# InkTime_schematic.net
KiCad netlist of a schematic drawn in EAGLE
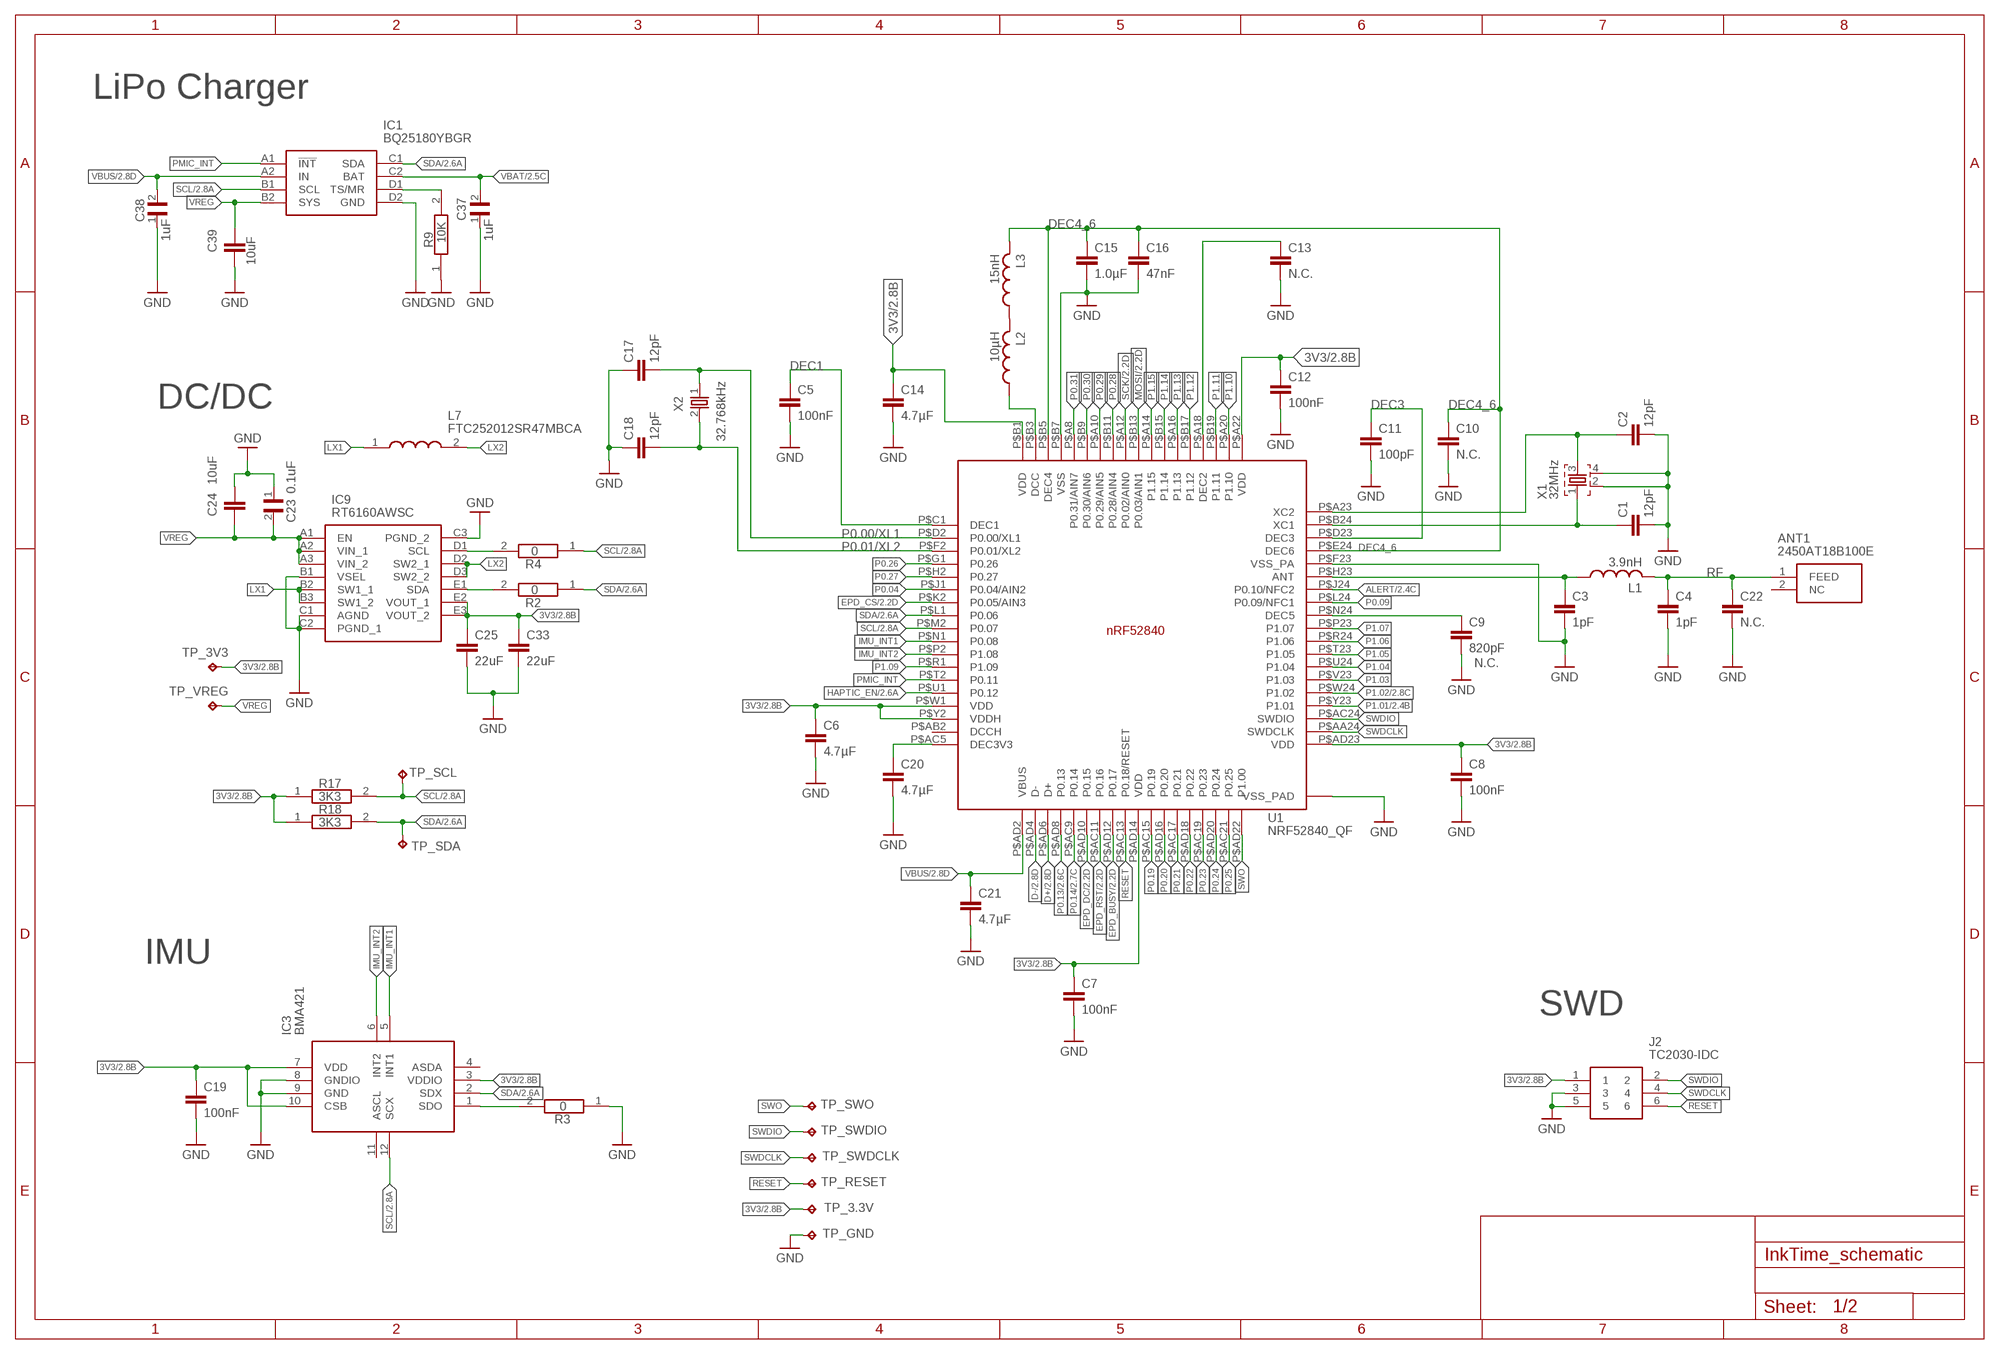
[diagram p0: schematic, sheet 1]
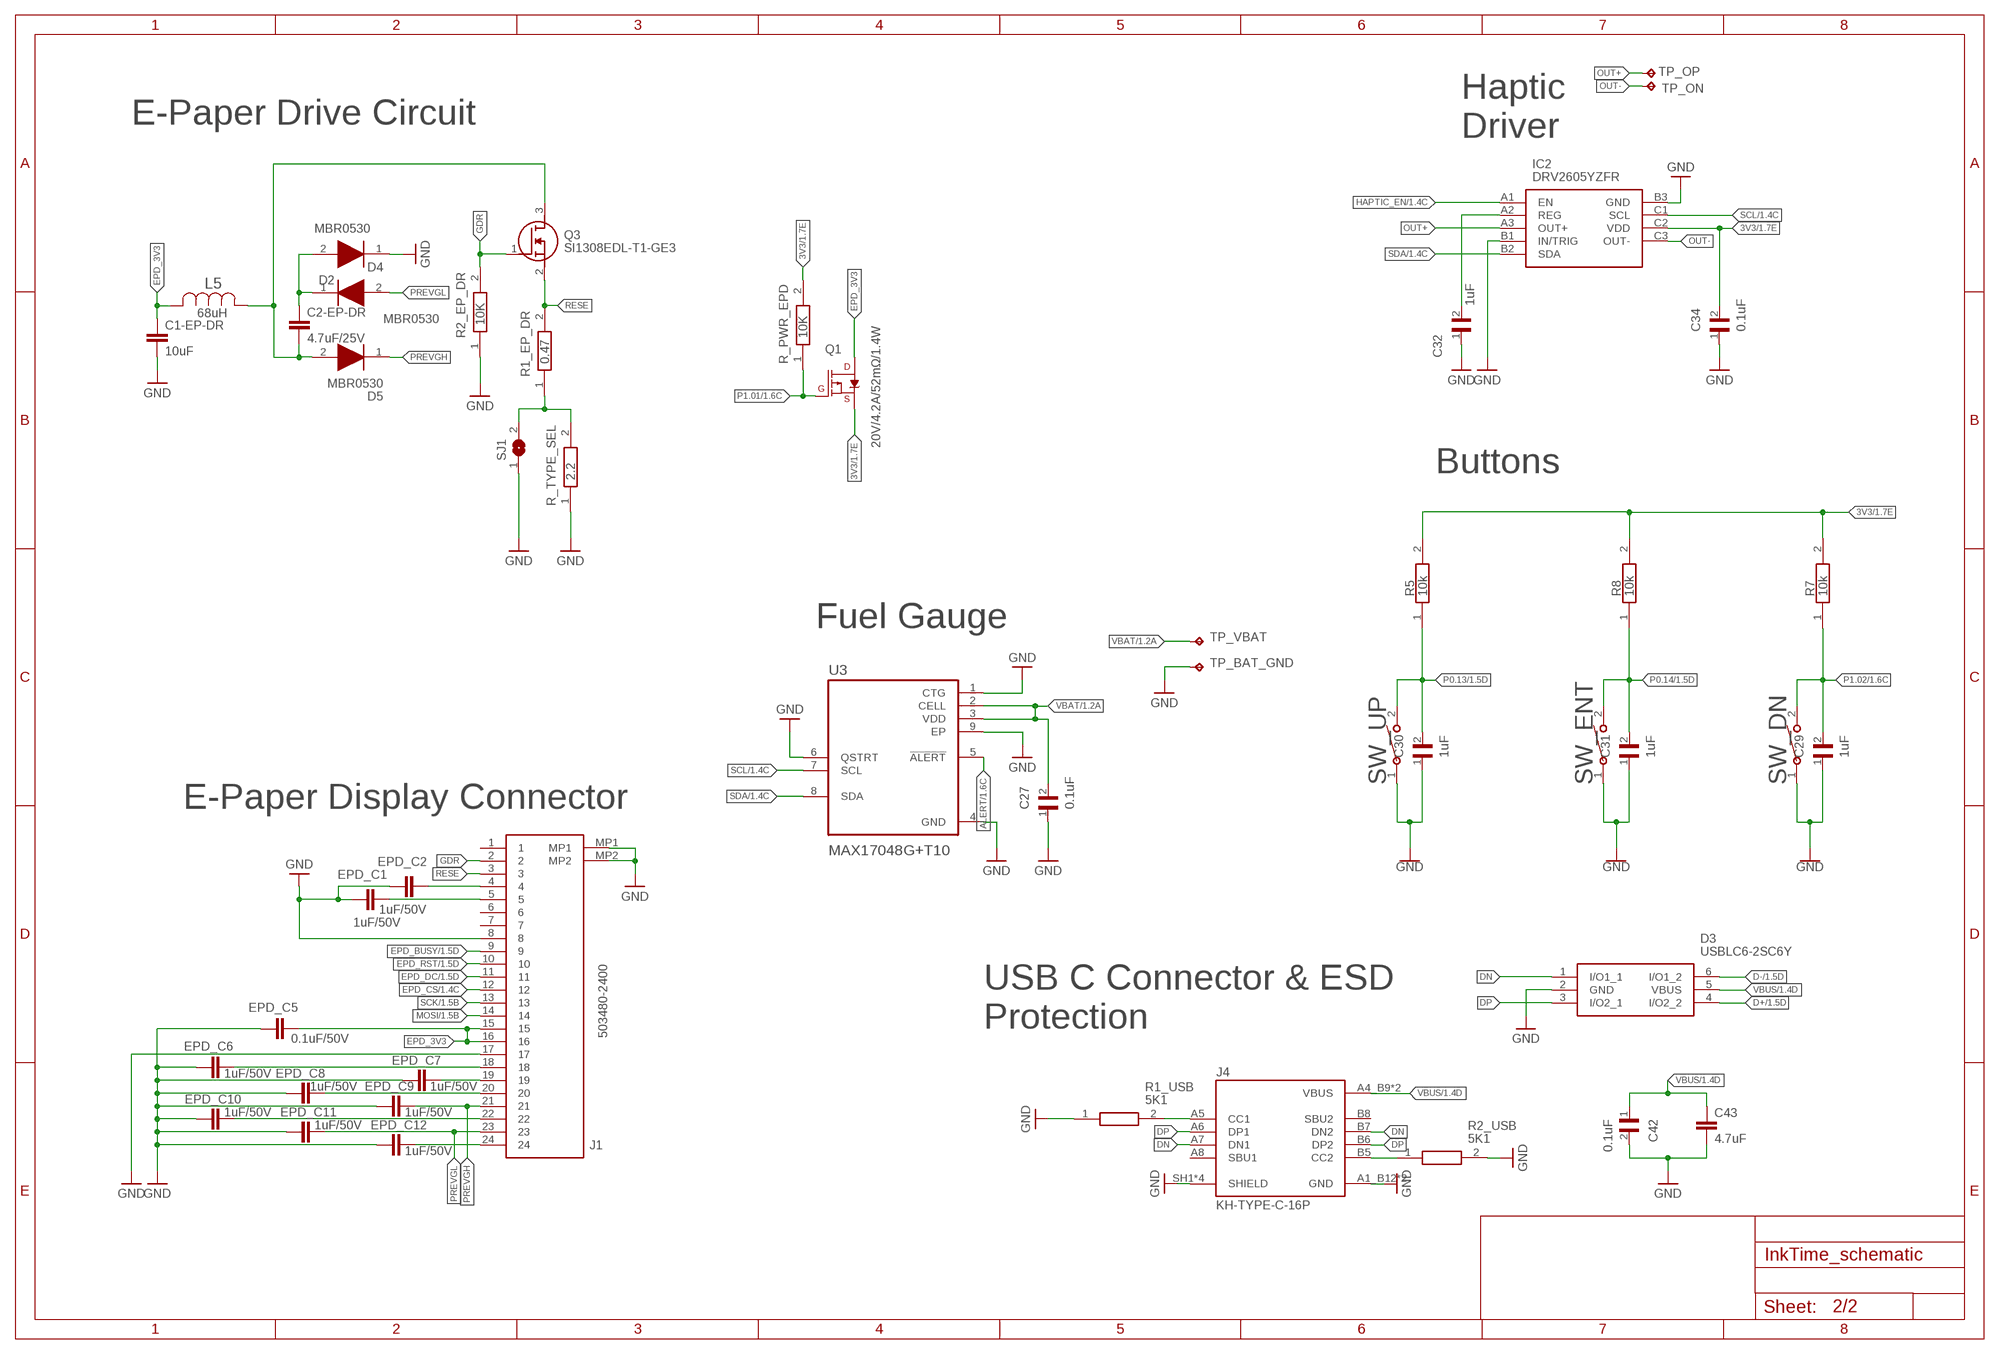
[diagram p1: schematic, sheet 2]

(export (version "E")
  (design (tool "Eeschema 10.0.6"))
  (components
    (comp (ref "ANT1")
      (value "2450AT18B100E")
      (footprint "eagle-import:2450AT18B100E_ANTC3216X140N")
      (fields (field (name "MOUSER_PART_NUMBER") "609-2450AT18B100E"))
      (libsource (lib "eagle-import") (part "2450AT18B100E_2450AT18B100E"))
    )
    (comp (ref "C1")
      (value "12pF")
      (footprint "eagle-import:NORDIC_NRF_3_RESC0201_L")
      (libsource (lib "eagle-import") (part "NORDIC_NRF_3_CAPACITOR_0201_L"))
    )
    (comp (ref "C2")
      (value "12pF")
      (footprint "eagle-import:NORDIC_NRF_3_RESC0201_L")
      (libsource (lib "eagle-import") (part "NORDIC_NRF_3_CAPACITOR_0201_L"))
    )
    (comp (ref "C3")
      (value "1pF")
      (footprint "eagle-import:NORDIC_NRF_3_RESC0201_L")
      (libsource (lib "eagle-import") (part "NORDIC_NRF_3_CAPACITOR_0201_L"))
    )
    (comp (ref "C4")
      (value "1pF")
      (footprint "eagle-import:NORDIC_NRF_3_RESC0201_L")
      (libsource (lib "eagle-import") (part "NORDIC_NRF_3_CAPACITOR_0201_L"))
    )
    (comp (ref "C5")
      (value "100nF")
      (footprint "eagle-import:NORDIC_NRF_3_RESC0201_L")
      (libsource (lib "eagle-import") (part "NORDIC_NRF_3_CAPACITOR_0201_L"))
    )
    (comp (ref "C6")
      (value "4.7µF")
      (footprint "eagle-import:NORDIC_NRF_3_RESC0201_L")
      (libsource (lib "eagle-import") (part "NORDIC_NRF_3_CAPACITOR_0201_L"))
    )
    (comp (ref "C7")
      (value "100nF")
      (footprint "eagle-import:NORDIC_NRF_3_RESC0201_L")
      (libsource (lib "eagle-import") (part "NORDIC_NRF_3_CAPACITOR_0201_L"))
    )
    (comp (ref "C8")
      (value "100nF")
      (footprint "eagle-import:NORDIC_NRF_3_RESC0201_L")
      (libsource (lib "eagle-import") (part "NORDIC_NRF_3_CAPACITOR_0201_L"))
    )
    (comp (ref "C9")
      (value "820pF")
      (footprint "eagle-import:NORDIC_NRF_3_RESC0201_L")
      (fields (field (name "STATUS") "N.C."))
      (libsource (lib "eagle-import") (part "NORDIC_NRF_3_CAPACITOR_0201_L"))
    )
    (comp (ref "C10")
      (value "N.C.")
      (footprint "eagle-import:NORDIC_NRF_3_RESC0201_L")
      (libsource (lib "eagle-import") (part "NORDIC_NRF_3_CAPACITOR_0201_L"))
    )
    (comp (ref "C11")
      (value "100pF")
      (footprint "eagle-import:NORDIC_NRF_3_RESC0201_L")
      (libsource (lib "eagle-import") (part "NORDIC_NRF_3_CAPACITOR_0201_L"))
    )
    (comp (ref "C12")
      (value "100nF")
      (footprint "eagle-import:NORDIC_NRF_3_RESC0201_L")
      (libsource (lib "eagle-import") (part "NORDIC_NRF_3_CAPACITOR_0201_L"))
    )
    (comp (ref "C13")
      (value "N.C.")
      (footprint "eagle-import:NORDIC_NRF_3_RESC0201_L")
      (libsource (lib "eagle-import") (part "NORDIC_NRF_3_CAPACITOR_0201_L"))
    )
    (comp (ref "C14")
      (value "4.7µF")
      (footprint "eagle-import:NORDIC_NRF_3_RESC0201_L")
      (libsource (lib "eagle-import") (part "NORDIC_NRF_3_CAPACITOR_0201_L"))
    )
    (comp (ref "C15")
      (value "1.0µF")
      (footprint "eagle-import:NORDIC_NRF_3_RESC0201_L")
      (libsource (lib "eagle-import") (part "NORDIC_NRF_3_CAPACITOR_0201_L"))
    )
    (comp (ref "C16")
      (value "47nF")
      (footprint "eagle-import:NORDIC_NRF_3_RESC0201_L")
      (libsource (lib "eagle-import") (part "NORDIC_NRF_3_CAPACITOR_0201_L"))
    )
    (comp (ref "C17")
      (value "12pF")
      (footprint "eagle-import:NORDIC_NRF_3_RESC0201_L")
      (libsource (lib "eagle-import") (part "NORDIC_NRF_3_CAPACITOR_0201_L"))
    )
    (comp (ref "C18")
      (value "12pF")
      (footprint "eagle-import:NORDIC_NRF_3_RESC0201_L")
      (libsource (lib "eagle-import") (part "NORDIC_NRF_3_CAPACITOR_0201_L"))
    )
    (comp (ref "C19")
      (value "100nF")
      (footprint "eagle-import:NORDIC_NRF_3_RESC0201_L")
      (libsource (lib "eagle-import") (part "NORDIC_NRF_3_CAPACITOR_0201_L"))
    )
    (comp (ref "C20")
      (value "4.7µF")
      (footprint "eagle-import:NORDIC_NRF_3_RESC0201_L")
      (libsource (lib "eagle-import") (part "NORDIC_NRF_3_CAPACITOR_0201_L"))
    )
    (comp (ref "C21")
      (value "4.7µF")
      (footprint "eagle-import:NORDIC_NRF_3_RESC0201_L")
      (libsource (lib "eagle-import") (part "NORDIC_NRF_3_CAPACITOR_0201_L"))
    )
    (comp (ref "C22")
      (value "N.C.")
      (footprint "eagle-import:NORDIC_NRF_3_RESC0201_L")
      (libsource (lib "eagle-import") (part "NORDIC_NRF_3_CAPACITOR_0201_L"))
    )
    (comp (ref "C23")
      (value "0.1uF")
      (footprint "eagle-import:GRM011R60J152KE01L_1_0201")
      (libsource (lib "eagle-import") (part "GRM011R60J152KE01L_1_GRM011R60J152KE01L"))
    )
    (comp (ref "C24")
      (value "10uF")
      (footprint "eagle-import:NORDIC_NRF_3_RESC0201_L")
      (libsource (lib "eagle-import") (part "NORDIC_NRF_3_CAPACITOR_0201_L"))
    )
    (comp (ref "C25")
      (value "22uF")
      (footprint "eagle-import:NORDIC_NRF_3_RESC0201_L")
      (libsource (lib "eagle-import") (part "NORDIC_NRF_3_CAPACITOR_0201_L"))
    )
    (comp (ref "C33")
      (value "22uF")
      (footprint "eagle-import:NORDIC_NRF_3_RESC0201_L")
      (libsource (lib "eagle-import") (part "NORDIC_NRF_3_CAPACITOR_0201_L"))
    )
    (comp (ref "C37")
      (value "1uF")
      (footprint "eagle-import:GRM011R60J152KE01L_1_0201")
      (libsource (lib "eagle-import") (part "GRM011R60J152KE01L_1_GRM011R60J152KE01L"))
    )
    (comp (ref "C38")
      (value "1uF")
      (footprint "eagle-import:GRM011R60J152KE01L_2_CAPC0201X13N")
      (fields (field (name "MF") "Murata") (field (name "MP") "GRM011R60J152KE01L"))
      (libsource (lib "eagle-import") (part "GRM011R60J152KE01L_2_GRM011R60J152KE01L"))
    )
    (comp (ref "C39")
      (value "10uF")
      (footprint "eagle-import:NORDIC_NRF_3_RESC0201_L")
      (libsource (lib "eagle-import") (part "NORDIC_NRF_3_CAPACITOR_0201_L"))
    )
    (comp (ref "IC1")
      (value "BQ25180YBGR")
      (footprint "eagle-import:BQ25180YBGR_BGA8C40P2X4_100X155X50")
      (fields (field (name "MOUSER_PART_NUMBER") "595-BQ25180YBGR"))
      (libsource (lib "eagle-import") (part "BQ25180YBGR_BQ25180YBGR"))
    )
    (comp (ref "IC3")
      (value "BMA421")
      (footprint "eagle-import:BMA423_BMA423")
      (fields (field (name "ARROW_PART_NUMBER") "BMA423") (field (name "MOUSER_PART_NUMBER") "262-BMA423"))
      (libsource (lib "eagle-import") (part "BMA423_BMA423"))
    )
    (comp (ref "IC9")
      (value "RT6160AWSC")
      (footprint "eagle-import:RT6160AWSC_BGA15C40P3X5_140X230X60")
      (fields (field (name "MOUSER_PART_NUMBER") "835-RT6160AWSC"))
      (libsource (lib "eagle-import") (part "RT6160AWSC_RT6160AWSC"))
    )
    (comp (ref "J2")
      (value "TC2030-IDC")
      (footprint "eagle-import:TC2030-IDC_TC2030IDC")
      (libsource (lib "eagle-import") (part "TC2030-IDC_TC2030-IDC"))
    )
    (comp (ref "L1")
      (value "3.9nH")
      (footprint "eagle-import:NORDIC_NRF_2_RESC0402_L")
      (libsource (lib "eagle-import") (part "NORDIC_NRF_2_INDUCTOR_0402_L"))
    )
    (comp (ref "L2")
      (value "10µH")
      (footprint "eagle-import:NORDIC_NRF_2_RESC0402_L")
      (libsource (lib "eagle-import") (part "NORDIC_NRF_2_INDUCTOR_0402_L"))
    )
    (comp (ref "L3")
      (value "15nH")
      (footprint "eagle-import:NORDIC_NRF_2_RESC0402_L")
      (libsource (lib "eagle-import") (part "NORDIC_NRF_2_INDUCTOR_0402_L"))
    )
    (comp (ref "L7")
      (value "FTC252012SR47MBCA")
      (footprint "eagle-import:MLP2016SR47MT0S1_INDC2016X100N")
      (libsource (lib "eagle-import") (part "MLP2016SR47MT0S1_FTC252012SR47MBCA"))
    )
    (comp (ref "R2")
      (value "0")
      (footprint "eagle-import:CPF0201D7K68C1_0201")
      (libsource (lib "eagle-import") (part "CPF0201D7K68C1_CPF0201D7K68C1"))
    )
    (comp (ref "R3")
      (value "0")
      (footprint "eagle-import:CPF0201D7K68C1_0201")
      (libsource (lib "eagle-import") (part "CPF0201D7K68C1_CPF0201D7K68C1"))
    )
    (comp (ref "R4")
      (value "0")
      (footprint "eagle-import:CPF0201D7K68C1_0201")
      (libsource (lib "eagle-import") (part "CPF0201D7K68C1_CPF0201D7K68C1"))
    )
    (comp (ref "R9")
      (value "10K")
      (footprint "eagle-import:CPF0201D7K68C1_0201")
      (libsource (lib "eagle-import") (part "CPF0201D7K68C1_CPF0201D7K68C1"))
    )
    (comp (ref "R17")
      (value "3K3")
      (footprint "eagle-import:CPF0201D7K68C1_0201")
      (libsource (lib "eagle-import") (part "CPF0201D7K68C1_CPF0201D7K68C1"))
    )
    (comp (ref "R18")
      (value "3K3")
      (footprint "eagle-import:CPF0201D7K68C1_0201")
      (libsource (lib "eagle-import") (part "CPF0201D7K68C1_CPF0201D7K68C1"))
    )
    (comp (ref "TP_3.3V")
      (value "HECTOR_WATCH_1_TPTP20R")
      (footprint "eagle-import:HECTOR_WATCH_1_TP20R")
      (libsource (lib "eagle-import") (part "HECTOR_WATCH_1_TPTP20R"))
    )
    (comp (ref "TP_3V3")
      (value "HECTOR_WATCH_1_TPTP20R")
      (footprint "eagle-import:HECTOR_WATCH_1_TP20R")
      (libsource (lib "eagle-import") (part "HECTOR_WATCH_1_TPTP20R"))
    )
    (comp (ref "TP_GND")
      (value "HECTOR_WATCH_1_TPTP20R")
      (footprint "eagle-import:HECTOR_WATCH_1_TP20R")
      (libsource (lib "eagle-import") (part "HECTOR_WATCH_1_TPTP20R"))
    )
    (comp (ref "TP_RESET")
      (value "HECTOR_WATCH_1_TPTP20R")
      (footprint "eagle-import:HECTOR_WATCH_1_TP20R")
      (libsource (lib "eagle-import") (part "HECTOR_WATCH_1_TPTP20R"))
    )
    (comp (ref "TP_SCL")
      (value "HECTOR_WATCH_1_TPTP20R")
      (footprint "eagle-import:HECTOR_WATCH_1_TP20R")
      (libsource (lib "eagle-import") (part "HECTOR_WATCH_1_TPTP20R"))
    )
    (comp (ref "TP_SDA")
      (value "HECTOR_WATCH_1_TPTP20R")
      (footprint "eagle-import:HECTOR_WATCH_1_TP20R")
      (libsource (lib "eagle-import") (part "HECTOR_WATCH_1_TPTP20R"))
    )
    (comp (ref "TP_SWDCLK")
      (value "HECTOR_WATCH_1_TPTP20R")
      (footprint "eagle-import:HECTOR_WATCH_1_TP20R")
      (libsource (lib "eagle-import") (part "HECTOR_WATCH_1_TPTP20R"))
    )
    (comp (ref "TP_SWDIO")
      (value "HECTOR_WATCH_1_TPTP20R")
      (footprint "eagle-import:HECTOR_WATCH_1_TP20R")
      (libsource (lib "eagle-import") (part "HECTOR_WATCH_1_TPTP20R"))
    )
    (comp (ref "TP_SWO")
      (value "HECTOR_WATCH_1_TPTP20R")
      (footprint "eagle-import:HECTOR_WATCH_1_TP20R")
      (libsource (lib "eagle-import") (part "HECTOR_WATCH_1_TPTP20R"))
    )
    (comp (ref "TP_VREG")
      (value "HECTOR_WATCH_1_TPTP20R")
      (footprint "eagle-import:HECTOR_WATCH_1_TP20R")
      (libsource (lib "eagle-import") (part "HECTOR_WATCH_1_TPTP20R"))
    )
    (comp (ref "U1")
      (value "NRF52840_QF")
      (footprint "eagle-import:NORDIC_NRF_4_AQFN50P700X700X85_HS-74N")
      (libsource (lib "eagle-import") (part "NORDIC_NRF_4_NRF52840_QF"))
    )
    (comp (ref "X1")
      (value "32MHz")
      (footprint "eagle-import:NORDIC_NRF_BT-XTAL_2016_N")
      (libsource (lib "eagle-import") (part "NORDIC_NRF_XTAL_32MHZ"))
    )
    (comp (ref "X2")
      (value "32.768kHz")
      (footprint "eagle-import:NORDIC_NRF_1_XTAL_3215_N")
      (libsource (lib "eagle-import") (part "NORDIC_NRF_1_XTAL_32KHZ"))
    )
    (comp (ref "C1-EP-DR")
      (value "10uF")
      (footprint "eagle-import:NORDIC_NRF_3_RESC0201_L")
      (libsource (lib "eagle-import") (part "NORDIC_NRF_3_CAPACITOR_0201_L"))
    )
    (comp (ref "C2-EP-DR")
      (value "4.7uF/25V")
      (footprint "eagle-import:NORDIC_NRF_3_RESC0201_L")
      (libsource (lib "eagle-import") (part "NORDIC_NRF_3_CAPACITOR_0201_L"))
    )
    (comp (ref "C27")
      (value "0.1uF")
      (footprint "eagle-import:GRM011R60J152KE01L_1_0201")
      (libsource (lib "eagle-import") (part "GRM011R60J152KE01L_1_GRM011R60J152KE01L"))
    )
    (comp (ref "C29")
      (value "1uF")
      (footprint "eagle-import:GRM011R60J152KE01L_1_0201")
      (libsource (lib "eagle-import") (part "GRM011R60J152KE01L_1_GRM011R60J152KE01L"))
    )
    (comp (ref "C30")
      (value "1uF")
      (footprint "eagle-import:GRM011R60J152KE01L_1_0201")
      (libsource (lib "eagle-import") (part "GRM011R60J152KE01L_1_GRM011R60J152KE01L"))
    )
    (comp (ref "C31")
      (value "1uF")
      (footprint "eagle-import:GRM011R60J152KE01L_1_0201")
      (libsource (lib "eagle-import") (part "GRM011R60J152KE01L_1_GRM011R60J152KE01L"))
    )
    (comp (ref "C32")
      (value "1uF")
      (footprint "eagle-import:GRM011R60J152KE01L_1_0201")
      (libsource (lib "eagle-import") (part "GRM011R60J152KE01L_1_GRM011R60J152KE01L"))
    )
    (comp (ref "C34")
      (value "0.1uF")
      (footprint "eagle-import:GRM011R60J152KE01L_1_0201")
      (libsource (lib "eagle-import") (part "GRM011R60J152KE01L_1_GRM011R60J152KE01L"))
    )
    (comp (ref "C42")
      (value "0.1uF")
      (footprint "eagle-import:GRM011R60J152KE01L_1_0201")
      (libsource (lib "eagle-import") (part "GRM011R60J152KE01L_1_GRM011R60J152KE01L"))
    )
    (comp (ref "C43")
      (value "4.7uF")
      (footprint "eagle-import:NORDIC_NRF_3_RESC0201_L")
      (libsource (lib "eagle-import") (part "NORDIC_NRF_3_CAPACITOR_0201_L"))
    )
    (comp (ref "D2")
      (value "MBR0530")
      (footprint "eagle-import:ESP32_C6_LIBRARY_5_SOD3716X135N")
      (fields (field (name "MF") "ON Semiconductor"))
      (libsource (lib "eagle-import") (part "ESP32_C6_LIBRARY_5_MBR0530"))
    )
    (comp (ref "D3")
      (value "USBLC6-2SC6Y")
      (footprint "eagle-import:ESP32_C6_LIBRARY_3_SOT95P280X145-6N")
      (fields (field (name "MF") "STMicroelectronics"))
      (libsource (lib "eagle-import") (part "ESP32_C6_LIBRARY_3_USBLC6-2SC6Y"))
    )
    (comp (ref "D4")
      (value "MBR0530")
      (footprint "eagle-import:ESP32_C6_LIBRARY_5_SOD3716X135N")
      (fields (field (name "MF") "ON Semiconductor"))
      (libsource (lib "eagle-import") (part "ESP32_C6_LIBRARY_5_MBR0530"))
    )
    (comp (ref "D5")
      (value "MBR0530")
      (footprint "eagle-import:ESP32_C6_LIBRARY_5_SOD3716X135N")
      (fields (field (name "MF") "ON Semiconductor"))
      (libsource (lib "eagle-import") (part "ESP32_C6_LIBRARY_5_MBR0530"))
    )
    (comp (ref "EPD_C1")
      (value "1uF/50V")
      (footprint "eagle-import:NORDIC_NRF_3_RESC0201_L")
      (libsource (lib "eagle-import") (part "NORDIC_NRF_3_CAPACITOR_0201_L"))
    )
    (comp (ref "EPD_C2")
      (value "1uF/50V")
      (footprint "eagle-import:NORDIC_NRF_3_RESC0201_L")
      (libsource (lib "eagle-import") (part "NORDIC_NRF_3_CAPACITOR_0201_L"))
    )
    (comp (ref "EPD_C5")
      (value "0.1uF/50V")
      (footprint "eagle-import:NORDIC_NRF_3_RESC0201_L")
      (libsource (lib "eagle-import") (part "NORDIC_NRF_3_CAPACITOR_0201_L"))
    )
    (comp (ref "EPD_C6")
      (value "1uF/50V")
      (footprint "eagle-import:NORDIC_NRF_3_RESC0201_L")
      (libsource (lib "eagle-import") (part "NORDIC_NRF_3_CAPACITOR_0201_L"))
    )
    (comp (ref "EPD_C7")
      (value "1uF/50V")
      (footprint "eagle-import:NORDIC_NRF_3_RESC0201_L")
      (libsource (lib "eagle-import") (part "NORDIC_NRF_3_CAPACITOR_0201_L"))
    )
    (comp (ref "EPD_C8")
      (value "1uF/50V")
      (footprint "eagle-import:NORDIC_NRF_3_RESC0201_L")
      (libsource (lib "eagle-import") (part "NORDIC_NRF_3_CAPACITOR_0201_L"))
    )
    (comp (ref "EPD_C9")
      (value "1uF/50V")
      (footprint "eagle-import:NORDIC_NRF_3_RESC0201_L")
      (libsource (lib "eagle-import") (part "NORDIC_NRF_3_CAPACITOR_0201_L"))
    )
    (comp (ref "EPD_C10")
      (value "1uF/50V")
      (footprint "eagle-import:NORDIC_NRF_3_RESC0201_L")
      (libsource (lib "eagle-import") (part "NORDIC_NRF_3_CAPACITOR_0201_L"))
    )
    (comp (ref "EPD_C11")
      (value "1uF/50V")
      (footprint "eagle-import:NORDIC_NRF_3_RESC0201_L")
      (libsource (lib "eagle-import") (part "NORDIC_NRF_3_CAPACITOR_0201_L"))
    )
    (comp (ref "EPD_C12")
      (value "1uF/50V")
      (footprint "eagle-import:NORDIC_NRF_3_RESC0201_L")
      (libsource (lib "eagle-import") (part "NORDIC_NRF_3_CAPACITOR_0201_L"))
    )
    (comp (ref "IC2")
      (value "DRV2605YZFR")
      (footprint "eagle-import:DRV2605YZFR_BGA9C50P3X3_144X144X62")
      (libsource (lib "eagle-import") (part "DRV2605YZFR_DRV2605YZFR"))
    )
    (comp (ref "J1")
      (value "503480-2400")
      (footprint "eagle-import:503480-2400_5034802400")
      (fields (field (name "MOUSER_PART_NUMBER") "538-503480-2400"))
      (libsource (lib "eagle-import") (part "503480-2400_503480-2400"))
    )
    (comp (ref "J4")
      (value "KH-TYPE-C-16P")
      (footprint "eagle-import:KH-TYPE-C-16P_KINGHELM_KH-TYPE-C-16P")
      (fields (field (name "MF") "kinghelm"))
      (libsource (lib "eagle-import") (part "KH-TYPE-C-16P_KH-TYPE-C-16P"))
    )
    (comp (ref "L5")
      (value "68uH")
      (footprint "eagle-import:ESP32_C6_LIBRARY_2_IND_4828-WE-TPC_WRE")
      (fields
        (field (name "MANUFACTURER_PART_NUMBER") "744043680")
        (field (name "COPYRIGHT") "Copyright (C) 2024 Ultra Librarian. All rights reserved.")
      )
      (libsource (lib "eagle-import") (part "ESP32_C6_LIBRARY_2_744043680IND_4828-WE-TPC_WRE"))
    )
    (comp (ref "Q1")
      (value "20V/4.2A/52mΩ/1.4W")
      (footprint "eagle-import:ESP32_C6_LIBRARY_4_ESP32_C6_LIBRARY_4_ESP32_C6_LIBRARY_4_ESP32_C6_LIBRARY_4_ESP32_WROVER_SPARKFUN-DISCRETESEMI_SOT23-3")
      (libsource (lib "eagle-import") (part "ESP32_C6_LIBRARY_4_ESP32_WROVER_SPARKFUN-DISCRETESEMI_MOSFET_PCH-DMG2305UX-7"))
    )
    (comp (ref "Q3")
      (value "SI1308EDL-T1-GE3")
      (footprint "eagle-import:ESP32_C6_LIBRARY_6_SOT65P210X110-3N")
      (fields (field (name "MF") "Vishay Siliconix"))
      (libsource (lib "eagle-import") (part "ESP32_C6_LIBRARY_6_SI1308EDL-T1-GE3"))
    )
    (comp (ref "R1_EP_DR")
      (value "0.47")
      (footprint "eagle-import:CPF0201D7K68C1_0201")
      (libsource (lib "eagle-import") (part "CPF0201D7K68C1_CPF0201D7K68C1"))
    )
    (comp (ref "R1_USB")
      (value "5K1")
      (footprint "eagle-import:CPF0201D7K68C1_0201")
      (libsource (lib "eagle-import") (part "CPF0201D7K68C1_CPF0201D7K68C1"))
    )
    (comp (ref "R2_EP_DR")
      (value "10K")
      (footprint "eagle-import:CPF0201D7K68C1_0201")
      (libsource (lib "eagle-import") (part "CPF0201D7K68C1_CPF0201D7K68C1"))
    )
    (comp (ref "R2_USB")
      (value "5K1")
      (footprint "eagle-import:CPF0201D7K68C1_0201")
      (libsource (lib "eagle-import") (part "CPF0201D7K68C1_CPF0201D7K68C1"))
    )
    (comp (ref "R5")
      (value "10k")
      (footprint "eagle-import:CPF0201D7K68C1_0201")
      (libsource (lib "eagle-import") (part "CPF0201D7K68C1_CPF0201D7K68C1"))
    )
    (comp (ref "R7")
      (value "10k")
      (footprint "eagle-import:CPF0201D7K68C1_0201")
      (libsource (lib "eagle-import") (part "CPF0201D7K68C1_CPF0201D7K68C1"))
    )
    (comp (ref "R8")
      (value "10k")
      (footprint "eagle-import:CPF0201D7K68C1_0201")
      (libsource (lib "eagle-import") (part "CPF0201D7K68C1_CPF0201D7K68C1"))
    )
    (comp (ref "R_PWR_EPD")
      (value "10K")
      (footprint "eagle-import:CPF0201D7K68C1_0201")
      (libsource (lib "eagle-import") (part "CPF0201D7K68C1_CPF0201D7K68C1"))
    )
    (comp (ref "R_TYPE_SEL")
      (value "2.2")
      (footprint "eagle-import:CPF0201D7K68C1_0201")
      (libsource (lib "eagle-import") (part "CPF0201D7K68C1_CPF0201D7K68C1"))
    )
    (comp (ref "SJ1")
      (value "ESP32_C6_LIBRARY_7_JUMPER_SJ")
      (footprint "eagle-import:ESP32_C6_LIBRARY_7_JUMPER_SJ")
      (libsource (lib "eagle-import") (part "ESP32_C6_LIBRARY_7_JUMPER_SJ"))
    )
    (comp (ref "SW_DN")
      (value "2025-10-22_07-23-44_LIBRARY_EVP-AKE31ASW_EVP-AKE31A_PAN")
      (footprint "eagle-import:2025-10-22_07-23-44_LIBRARY_SW_EVP-AKE31A_PAN")
      (fields
        (field (name "MANUFACTURER_PART_NUMBER") "EVP-AKE31A")
        (field (name "COPYRIGHT") "Copyright (C) 2025 Ultra Librarian. All rights reserved.")
      )
      (libsource (lib "eagle-import") (part "2025-10-22_07-23-44_LIBRARY_EVP-AKE31ASW_EVP-AKE31A_PAN"))
    )
    (comp (ref "SW_ENT")
      (value "2025-10-22_07-23-44_LIBRARY_EVP-AKE31ASW_EVP-AKE31A_PAN")
      (footprint "eagle-import:2025-10-22_07-23-44_LIBRARY_SW_EVP-AKE31A_PAN")
      (fields
        (field (name "MANUFACTURER_PART_NUMBER") "EVP-AKE31A")
        (field (name "COPYRIGHT") "Copyright (C) 2025 Ultra Librarian. All rights reserved.")
      )
      (libsource (lib "eagle-import") (part "2025-10-22_07-23-44_LIBRARY_EVP-AKE31ASW_EVP-AKE31A_PAN"))
    )
    (comp (ref "SW_UP")
      (value "2025-10-22_07-23-44_LIBRARY_EVP-AKE31ASW_EVP-AKE31A_PAN")
      (footprint "eagle-import:2025-10-22_07-23-44_LIBRARY_SW_EVP-AKE31A_PAN")
      (fields
        (field (name "MANUFACTURER_PART_NUMBER") "EVP-AKE31A")
        (field (name "COPYRIGHT") "Copyright (C) 2025 Ultra Librarian. All rights reserved.")
      )
      (libsource (lib "eagle-import") (part "2025-10-22_07-23-44_LIBRARY_EVP-AKE31ASW_EVP-AKE31A_PAN"))
    )
    (comp (ref "TP_BAT_GND")
      (value "HECTOR_WATCH_1_TPTP20R")
      (footprint "eagle-import:HECTOR_WATCH_1_TP20R")
      (libsource (lib "eagle-import") (part "HECTOR_WATCH_1_TPTP20R"))
    )
    (comp (ref "TP_ON")
      (value "HECTOR_WATCH_1_TPTP20R")
      (footprint "eagle-import:HECTOR_WATCH_1_TP20R")
      (libsource (lib "eagle-import") (part "HECTOR_WATCH_1_TPTP20R"))
    )
    (comp (ref "TP_OP")
      (value "HECTOR_WATCH_1_TPTP20R")
      (footprint "eagle-import:HECTOR_WATCH_1_TP20R")
      (libsource (lib "eagle-import") (part "HECTOR_WATCH_1_TPTP20R"))
    )
    (comp (ref "TP_VBAT")
      (value "HECTOR_WATCH_1_TPTP20R")
      (footprint "eagle-import:HECTOR_WATCH_1_TP20R")
      (libsource (lib "eagle-import") (part "HECTOR_WATCH_1_TPTP20R"))
    )
    (comp (ref "U3")
      (value "MAX17048G+T10")
      (footprint "eagle-import:ESP32_C6_LIBRARY_SON50P200X200X80-9N")
      (fields (field (name "MF") "Analog Devices"))
      (libsource (lib "eagle-import") (part "ESP32_C6_LIBRARY_MAX17048G+T10"))
    )
  )
  (nets
    (net (code "1") (name "3V3") (class "Default")
      (node (ref "C12") (pin "1") (pinfunction "1_1") (pintype "passive"))
      (node (ref "C14") (pin "1") (pinfunction "1_1") (pintype "passive"))
      (node (ref "C19") (pin "1") (pinfunction "1_1") (pintype "passive"))
      (node (ref "C25") (pin "1") (pinfunction "1_1") (pintype "passive"))
      (node (ref "C33") (pin "1") (pinfunction "1_1") (pintype "passive"))
      (node (ref "C34") (pin "2") (pinfunction "2_2") (pintype "passive"))
      (node (ref "C6") (pin "1") (pinfunction "1_1") (pintype "passive"))
      (node (ref "C7") (pin "1") (pinfunction "1_1") (pintype "passive"))
      (node (ref "C8") (pin "1") (pinfunction "1_1") (pintype "passive"))
      (node (ref "IC2") (pin "C2") (pinfunction "VDD_C2") (pintype "bidirectional"))
      (node (ref "IC3") (pin "10") (pinfunction "CSB_10") (pintype "bidirectional"))
      (node (ref "IC3") (pin "3") (pinfunction "VDDIO_3") (pintype "bidirectional"))
      (node (ref "IC3") (pin "7") (pinfunction "VDD_7") (pintype "bidirectional"))
      (node (ref "IC9") (pin "E2") (pinfunction "VOUT_1_E2") (pintype "bidirectional"))
      (node (ref "IC9") (pin "E3") (pinfunction "VOUT_2_E3") (pintype "bidirectional"))
      (node (ref "J2") (pin "1") (pinfunction "1_1") (pintype "bidirectional"))
      (node (ref "Q1") (pin "2") (pinfunction "S_2") (pintype "bidirectional"))
      (node (ref "R17") (pin "1") (pinfunction "1_1") (pintype "bidirectional"))
      (node (ref "R18") (pin "1") (pinfunction "1_1") (pintype "bidirectional"))
      (node (ref "R5") (pin "2") (pinfunction "2_2") (pintype "bidirectional"))
      (node (ref "R7") (pin "2") (pinfunction "2_2") (pintype "bidirectional"))
      (node (ref "R8") (pin "2") (pinfunction "2_2") (pintype "bidirectional"))
      (node (ref "R_PWR_EPD") (pin "2") (pinfunction "2_2") (pintype "bidirectional"))
      (node (ref "TP_3.3V") (pin "TP") (pinfunction "TP_TP") (pintype "input"))
      (node (ref "TP_3V3") (pin "TP") (pinfunction "TP_TP") (pintype "input"))
      (node (ref "U1") (pin "P$A22") (pinfunction "VDD_P$A22") (pintype "power_in"))
      (node (ref "U1") (pin "P$AD14") (pinfunction "VDD_P$AD14") (pintype "power_in"))
      (node (ref "U1") (pin "P$AD23") (pinfunction "VDD_P$AD23") (pintype "power_in"))
      (node (ref "U1") (pin "P$B1") (pinfunction "VDD_P$B1") (pintype "power_in"))
      (node (ref "U1") (pin "P$W1") (pinfunction "VDD_P$W1") (pintype "power_in"))
      (node (ref "U1") (pin "P$Y2") (pinfunction "VDDH_P$Y2") (pintype "power_in"))
    )
    (net (code "2") (name "ALERT") (class "Default")
      (node (ref "U1") (pin "P$J24") (pinfunction "P0.10/NFC2_P$J24") (pintype "bidirectional"))
      (node (ref "U3") (pin "5") (pinfunction "~{ALERT}_5") (pintype "output"))
    )
    (net (code "3") (name "D+") (class "Default")
      (node (ref "D3") (pin "4") (pinfunction "I/O2_2_4") (pintype "bidirectional"))
      (node (ref "U1") (pin "P$AD6") (pinfunction "D+_P$AD6") (pintype "bidirectional"))
    )
    (net (code "4") (name "D-") (class "Default")
      (node (ref "D3") (pin "6") (pinfunction "I/O1_2_6") (pintype "bidirectional"))
      (node (ref "U1") (pin "P$AD4") (pinfunction "D-_P$AD4") (pintype "bidirectional"))
    )
    (net (code "5") (name "DEC1") (class "Default")
      (node (ref "C5") (pin "1") (pinfunction "1_1") (pintype "passive"))
      (node (ref "U1") (pin "P$C1") (pinfunction "DEC1_P$C1") (pintype "power_in"))
    )
    (net (code "6") (name "DEC3") (class "Default")
      (node (ref "C11") (pin "1") (pinfunction "1_1") (pintype "passive"))
      (node (ref "U1") (pin "P$D23") (pinfunction "DEC3_P$D23") (pintype "bidirectional"))
    )
    (net (code "7") (name "DEC4_6") (class "Default")
      (node (ref "C10") (pin "1") (pinfunction "1_1") (pintype "passive"))
      (node (ref "C15") (pin "1") (pinfunction "1_1") (pintype "passive"))
      (node (ref "C16") (pin "1") (pinfunction "1_1") (pintype "passive"))
      (node (ref "L3") (pin "2") (pinfunction "2_2") (pintype "passive"))
      (node (ref "U1") (pin "P$B5") (pinfunction "DEC4_P$B5") (pintype "power_in"))
      (node (ref "U1") (pin "P$E24") (pinfunction "DEC6_P$E24") (pintype "bidirectional"))
    )
    (net (code "8") (name "DN") (class "Default")
      (node (ref "D3") (pin "1") (pinfunction "I/O1_1_1") (pintype "bidirectional"))
      (node (ref "J4") (pin "A7") (pinfunction "DN1_A7") (pintype "bidirectional"))
      (node (ref "J4") (pin "B7") (pinfunction "DN2_B7") (pintype "bidirectional"))
    )
    (net (code "9") (name "DP") (class "Default")
      (node (ref "D3") (pin "3") (pinfunction "I/O2_1_3") (pintype "bidirectional"))
      (node (ref "J4") (pin "A6") (pinfunction "DP1_A6") (pintype "bidirectional"))
      (node (ref "J4") (pin "B6") (pinfunction "DP2_B6") (pintype "bidirectional"))
    )
    (net (code "10") (name "EPD_3V3") (class "Default")
      (node (ref "C1-EP-DR") (pin "1") (pinfunction "1_1") (pintype "passive"))
      (node (ref "EPD_C5") (pin "2") (pinfunction "2_2") (pintype "passive"))
      (node (ref "J1") (pin "15") (pinfunction "15_15") (pintype "bidirectional"))
      (node (ref "J1") (pin "16") (pinfunction "16_16") (pintype "bidirectional"))
      (node (ref "L5") (pin "2") (pinfunction "2_2") (pintype "passive"))
      (node (ref "Q1") (pin "3") (pinfunction "D_3") (pintype "bidirectional"))
    )
    (net (code "11") (name "EPD_BUSY") (class "Default")
      (node (ref "J1") (pin "9") (pinfunction "9_9") (pintype "bidirectional"))
      (node (ref "U1") (pin "P$AD12") (pinfunction "P0.17_P$AD12") (pintype "bidirectional"))
    )
    (net (code "12") (name "EPD_CS") (class "Default")
      (node (ref "J1") (pin "12") (pinfunction "12_12") (pintype "bidirectional"))
      (node (ref "U1") (pin "P$K2") (pinfunction "P0.05/AIN3_P$K2") (pintype "bidirectional"))
    )
    (net (code "13") (name "EPD_DC") (class "Default")
      (node (ref "J1") (pin "11") (pinfunction "11_11") (pintype "bidirectional"))
      (node (ref "U1") (pin "P$AD10") (pinfunction "P0.15_P$AD10") (pintype "bidirectional"))
    )
    (net (code "14") (name "EPD_RST") (class "Default")
      (node (ref "J1") (pin "10") (pinfunction "10_10") (pintype "bidirectional"))
      (node (ref "U1") (pin "P$AC11") (pinfunction "P0.16_P$AC11") (pintype "bidirectional"))
    )
    (net (code "15") (name "GDR") (class "Default")
      (node (ref "J1") (pin "2") (pinfunction "2_2") (pintype "bidirectional"))
      (node (ref "Q3") (pin "1") (pinfunction "G_1") (pintype "bidirectional"))
      (node (ref "R2_EP_DR") (pin "2") (pinfunction "2_2") (pintype "bidirectional"))
    )
    (net (code "16") (name "GND") (class "Default")
      (node (ref "C1") (pin "2") (pinfunction "2_2") (pintype "passive"))
      (node (ref "C1-EP-DR") (pin "2") (pinfunction "2_2") (pintype "passive"))
      (node (ref "C10") (pin "2") (pinfunction "2_2") (pintype "passive"))
      (node (ref "C11") (pin "2") (pinfunction "2_2") (pintype "passive"))
      (node (ref "C12") (pin "2") (pinfunction "2_2") (pintype "passive"))
      (node (ref "C13") (pin "2") (pinfunction "2_2") (pintype "passive"))
      (node (ref "C14") (pin "2") (pinfunction "2_2") (pintype "passive"))
      (node (ref "C15") (pin "2") (pinfunction "2_2") (pintype "passive"))
      (node (ref "C16") (pin "2") (pinfunction "2_2") (pintype "passive"))
      (node (ref "C17") (pin "1") (pinfunction "1_1") (pintype "passive"))
      (node (ref "C18") (pin "1") (pinfunction "1_1") (pintype "passive"))
      (node (ref "C19") (pin "2") (pinfunction "2_2") (pintype "passive"))
      (node (ref "C2") (pin "2") (pinfunction "2_2") (pintype "passive"))
      (node (ref "C20") (pin "2") (pinfunction "2_2") (pintype "passive"))
      (node (ref "C21") (pin "2") (pinfunction "2_2") (pintype "passive"))
      (node (ref "C22") (pin "2") (pinfunction "2_2") (pintype "passive"))
      (node (ref "C23") (pin "1") (pinfunction "1_1") (pintype "passive"))
      (node (ref "C24") (pin "1") (pinfunction "1_1") (pintype "passive"))
      (node (ref "C25") (pin "2") (pinfunction "2_2") (pintype "passive"))
      (node (ref "C27") (pin "1") (pinfunction "1_1") (pintype "passive"))
      (node (ref "C29") (pin "1") (pinfunction "1_1") (pintype "passive"))
      (node (ref "C3") (pin "2") (pinfunction "2_2") (pintype "passive"))
      (node (ref "C30") (pin "1") (pinfunction "1_1") (pintype "passive"))
      (node (ref "C31") (pin "1") (pinfunction "1_1") (pintype "passive"))
      (node (ref "C32") (pin "1") (pinfunction "1_1") (pintype "passive"))
      (node (ref "C33") (pin "2") (pinfunction "2_2") (pintype "passive"))
      (node (ref "C34") (pin "1") (pinfunction "1_1") (pintype "passive"))
      (node (ref "C37") (pin "1") (pinfunction "1_1") (pintype "passive"))
      (node (ref "C38") (pin "1") (pinfunction "1_1") (pintype "passive"))
      (node (ref "C39") (pin "2") (pinfunction "2_2") (pintype "passive"))
      (node (ref "C4") (pin "2") (pinfunction "2_2") (pintype "passive"))
      (node (ref "C42") (pin "2") (pinfunction "2_2") (pintype "passive"))
      (node (ref "C43") (pin "2") (pinfunction "2_2") (pintype "passive"))
      (node (ref "C5") (pin "2") (pinfunction "2_2") (pintype "passive"))
      (node (ref "C6") (pin "2") (pinfunction "2_2") (pintype "passive"))
      (node (ref "C7") (pin "2") (pinfunction "2_2") (pintype "passive"))
      (node (ref "C8") (pin "2") (pinfunction "2_2") (pintype "passive"))
      (node (ref "C9") (pin "2") (pinfunction "2_2") (pintype "passive"))
      (node (ref "D3") (pin "2") (pinfunction "GND_2") (pintype "bidirectional"))
      (node (ref "D4") (pin "1") (pinfunction "K_1") (pintype "bidirectional"))
      (node (ref "EPD_C1") (pin "1") (pinfunction "1_1") (pintype "passive"))
      (node (ref "EPD_C10") (pin "1") (pinfunction "1_1") (pintype "passive"))
      (node (ref "EPD_C11") (pin "1") (pinfunction "1_1") (pintype "passive"))
      (node (ref "EPD_C12") (pin "1") (pinfunction "1_1") (pintype "passive"))
      (node (ref "EPD_C2") (pin "1") (pinfunction "1_1") (pintype "passive"))
      (node (ref "EPD_C5") (pin "1") (pinfunction "1_1") (pintype "passive"))
      (node (ref "EPD_C6") (pin "1") (pinfunction "1_1") (pintype "passive"))
      (node (ref "EPD_C7") (pin "1") (pinfunction "1_1") (pintype "passive"))
      (node (ref "EPD_C8") (pin "1") (pinfunction "1_1") (pintype "passive"))
      (node (ref "EPD_C9") (pin "1") (pinfunction "1_1") (pintype "passive"))
      (node (ref "IC1") (pin "D2") (pinfunction "GND_D2") (pintype "bidirectional"))
      (node (ref "IC2") (pin "B1") (pinfunction "IN/TRIG_B1") (pintype "bidirectional"))
      (node (ref "IC2") (pin "B3") (pinfunction "GND_B3") (pintype "bidirectional"))
      (node (ref "IC3") (pin "8") (pinfunction "GNDIO_8") (pintype "bidirectional"))
      (node (ref "IC3") (pin "9") (pinfunction "GND_9") (pintype "bidirectional"))
      (node (ref "IC9") (pin "B1") (pinfunction "VSEL_B1") (pintype "bidirectional"))
      (node (ref "IC9") (pin "C1") (pinfunction "AGND_C1") (pintype "bidirectional"))
      (node (ref "IC9") (pin "C2") (pinfunction "PGND_1_C2") (pintype "bidirectional"))
      (node (ref "IC9") (pin "C3") (pinfunction "PGND_2_C3") (pintype "bidirectional"))
      (node (ref "J1") (pin "17") (pinfunction "17_17") (pintype "bidirectional"))
      (node (ref "J1") (pin "8") (pinfunction "8_8") (pintype "bidirectional"))
      (node (ref "J1") (pin "MP1") (pinfunction "MP1_MP1") (pintype "bidirectional"))
      (node (ref "J1") (pin "MP2") (pinfunction "MP2_MP2") (pintype "bidirectional"))
      (node (ref "J2") (pin "3") (pinfunction "3_3") (pintype "bidirectional"))
      (node (ref "J2") (pin "5") (pinfunction "5_5") (pintype "bidirectional"))
      (node (ref "J4") (pin "A12_B1") (pinfunction "GND_A12_B1") (pintype "power_in"))
      (node (ref "J4") (pin "A1_B12") (pinfunction "GND_A1_B12") (pintype "power_in"))
      (node (ref "J4") (pin "SH1") (pinfunction "SHIELD_SH1") (pintype "passive"))
      (node (ref "J4") (pin "SH2") (pinfunction "SHIELD_SH2") (pintype "passive"))
      (node (ref "J4") (pin "SH3") (pinfunction "SHIELD_SH3") (pintype "passive"))
      (node (ref "J4") (pin "SH4") (pinfunction "SHIELD_SH4") (pintype "passive"))
      (node (ref "R1_USB") (pin "1") (pinfunction "1_1") (pintype "bidirectional"))
      (node (ref "R2_EP_DR") (pin "1") (pinfunction "1_1") (pintype "bidirectional"))
      (node (ref "R2_USB") (pin "2") (pinfunction "2_2") (pintype "bidirectional"))
      (node (ref "R3") (pin "1") (pinfunction "1_1") (pintype "bidirectional"))
      (node (ref "R9") (pin "1") (pinfunction "1_1") (pintype "bidirectional"))
      (node (ref "R_TYPE_SEL") (pin "1") (pinfunction "1_1") (pintype "bidirectional"))
      (node (ref "SJ1") (pin "1") (pinfunction "1_1") (pintype "passive"))
      (node (ref "SW_DN") (pin "1") (pinfunction "1_1") (pintype "passive"))
      (node (ref "SW_ENT") (pin "1") (pinfunction "1_1") (pintype "passive"))
      (node (ref "SW_UP") (pin "1") (pinfunction "1_1") (pintype "passive"))
      (node (ref "TP_BAT_GND") (pin "TP") (pinfunction "TP_TP") (pintype "input"))
      (node (ref "TP_GND") (pin "TP") (pinfunction "TP_TP") (pintype "input"))
      (node (ref "U1") (pin "P$74") (pinfunction "VSS_PAD_P$74") (pintype "bidirectional"))
      (node (ref "U1") (pin "P$75") (pinfunction "VSS_PAD_P$75") (pintype "bidirectional"))
      (node (ref "U1") (pin "P$76") (pinfunction "VSS_PAD_P$76") (pintype "bidirectional"))
      (node (ref "U1") (pin "P$77") (pinfunction "VSS_PAD_P$77") (pintype "bidirectional"))
      (node (ref "U1") (pin "P$78") (pinfunction "VSS_PAD_P$78") (pintype "bidirectional"))
      (node (ref "U1") (pin "P$79") (pinfunction "VSS_PAD_P$79") (pintype "bidirectional"))
      (node (ref "U1") (pin "P$80") (pinfunction "VSS_PAD_P$80") (pintype "bidirectional"))
      (node (ref "U1") (pin "P$81") (pinfunction "VSS_PAD_P$81") (pintype "bidirectional"))
      (node (ref "U1") (pin "P$82") (pinfunction "VSS_PAD_P$82") (pintype "bidirectional"))
      (node (ref "U1") (pin "P$83") (pinfunction "VSS_PAD_P$83") (pintype "bidirectional"))
      (node (ref "U1") (pin "P$84") (pinfunction "VSS_PAD_P$84") (pintype "bidirectional"))
      (node (ref "U1") (pin "P$85") (pinfunction "VSS_PAD_P$85") (pintype "bidirectional"))
      (node (ref "U1") (pin "P$86") (pinfunction "VSS_PAD_P$86") (pintype "bidirectional"))
      (node (ref "U1") (pin "P$87") (pinfunction "VSS_PAD_P$87") (pintype "bidirectional"))
      (node (ref "U1") (pin "P$88") (pinfunction "VSS_PAD_P$88") (pintype "bidirectional"))
      (node (ref "U1") (pin "P$89") (pinfunction "VSS_PAD_P$89") (pintype "bidirectional"))
      (node (ref "U1") (pin "P$90") (pinfunction "VSS_PAD_P$90") (pintype "bidirectional"))
      (node (ref "U1") (pin "P$B7") (pinfunction "VSS_P$B7") (pintype "power_in"))
      (node (ref "U1") (pin "P$F23") (pinfunction "VSS_PA_P$F23") (pintype "bidirectional"))
      (node (ref "U3") (pin "1") (pinfunction "CTG_1") (pintype "power_in"))
      (node (ref "U3") (pin "4") (pinfunction "GND_4") (pintype "power_in"))
      (node (ref "U3") (pin "6") (pinfunction "QSTRT_6") (pintype "input"))
      (node (ref "U3") (pin "9") (pinfunction "EP_9") (pintype "power_in"))
      (node (ref "X1") (pin "2") (pinfunction "2_2") (pintype "passive"))
      (node (ref "X1") (pin "4") (pinfunction "4_4") (pintype "passive"))
    )
    (net (code "17") (name "HAPTIC_EN") (class "Default")
      (node (ref "IC2") (pin "A1") (pinfunction "EN_A1") (pintype "bidirectional"))
      (node (ref "U1") (pin "P$U1") (pinfunction "P0.12_P$U1") (pintype "bidirectional"))
    )
    (net (code "18") (name "IMU_INT1") (class "Default")
      (node (ref "IC3") (pin "5") (pinfunction "INT1_5") (pintype "bidirectional"))
      (node (ref "U1") (pin "P$N1") (pinfunction "P0.08_P$N1") (pintype "bidirectional"))
    )
    (net (code "19") (name "IMU_INT2") (class "Default")
      (node (ref "IC3") (pin "6") (pinfunction "INT2_6") (pintype "bidirectional"))
      (node (ref "U1") (pin "P$P2") (pinfunction "P1.08_P$P2") (pintype "bidirectional"))
    )
    (net (code "20") (name "LX1") (class "Default")
      (node (ref "IC9") (pin "B2") (pinfunction "SW1_1_B2") (pintype "bidirectional"))
      (node (ref "IC9") (pin "B3") (pinfunction "SW1_2_B3") (pintype "bidirectional"))
      (node (ref "L7") (pin "1") (pinfunction "1_1") (pintype "bidirectional"))
    )
    (net (code "21") (name "LX2") (class "Default")
      (node (ref "IC9") (pin "D2") (pinfunction "SW2_1_D2") (pintype "bidirectional"))
      (node (ref "IC9") (pin "D3") (pinfunction "SW2_2_D3") (pintype "bidirectional"))
      (node (ref "L7") (pin "2") (pinfunction "2_2") (pintype "bidirectional"))
    )
    (net (code "22") (name "MOSI") (class "Default")
      (node (ref "J1") (pin "14") (pinfunction "14_14") (pintype "bidirectional"))
      (node (ref "U1") (pin "P$B13") (pinfunction "P0.03/AIN1_P$B13") (pintype "bidirectional"))
    )
    (net (code "23") (name "Net-(D2-K)") (class "Default")
      (node (ref "C2-EP-DR") (pin "1") (pinfunction "1_1") (pintype "passive"))
      (node (ref "D2") (pin "1") (pinfunction "K_1") (pintype "bidirectional"))
      (node (ref "D4") (pin "2") (pinfunction "A_2") (pintype "bidirectional"))
    )
    (net (code "24") (name "Net-(D5-A)") (class "Default")
      (node (ref "C2-EP-DR") (pin "2") (pinfunction "2_2") (pintype "passive"))
      (node (ref "D5") (pin "2") (pinfunction "A_2") (pintype "bidirectional"))
      (node (ref "L5") (pin "1") (pinfunction "1_1") (pintype "passive"))
      (node (ref "Q3") (pin "3") (pinfunction "D_3") (pintype "bidirectional"))
    )
    (net (code "25") (name "Net-(EPD_C1-Pad2)") (class "Default")
      (node (ref "EPD_C1") (pin "2") (pinfunction "2_2") (pintype "passive"))
      (node (ref "J1") (pin "5") (pinfunction "5_5") (pintype "bidirectional"))
    )
    (net (code "26") (name "Net-(EPD_C2-Pad2)") (class "Default")
      (node (ref "EPD_C2") (pin "2") (pinfunction "2_2") (pintype "passive"))
      (node (ref "J1") (pin "4") (pinfunction "4_4") (pintype "bidirectional"))
    )
    (net (code "27") (name "Net-(EPD_C6-Pad2)") (class "Default")
      (node (ref "EPD_C6") (pin "2") (pinfunction "2_2") (pintype "passive"))
      (node (ref "J1") (pin "18") (pinfunction "18_18") (pintype "bidirectional"))
    )
    (net (code "28") (name "Net-(EPD_C7-Pad2)") (class "Default")
      (node (ref "EPD_C7") (pin "2") (pinfunction "2_2") (pintype "passive"))
      (node (ref "J1") (pin "19") (pinfunction "19_19") (pintype "bidirectional"))
    )
    (net (code "29") (name "Net-(EPD_C8-Pad2)") (class "Default")
      (node (ref "EPD_C8") (pin "2") (pinfunction "2_2") (pintype "passive"))
      (node (ref "J1") (pin "20") (pinfunction "20_20") (pintype "bidirectional"))
    )
    (net (code "30") (name "Net-(EPD_C10-Pad2)") (class "Default")
      (node (ref "EPD_C10") (pin "2") (pinfunction "2_2") (pintype "passive"))
      (node (ref "J1") (pin "22") (pinfunction "22_22") (pintype "bidirectional"))
    )
    (net (code "31") (name "Net-(EPD_C12-Pad2)") (class "Default")
      (node (ref "EPD_C12") (pin "2") (pinfunction "2_2") (pintype "passive"))
      (node (ref "J1") (pin "24") (pinfunction "24_24") (pintype "bidirectional"))
    )
    (net (code "32") (name "Net-(IC1-TS{slash}MR)") (class "Default")
      (node (ref "IC1") (pin "D1") (pinfunction "TS/MR_D1") (pintype "bidirectional"))
      (node (ref "R9") (pin "2") (pinfunction "2_2") (pintype "bidirectional"))
    )
    (net (code "33") (name "Net-(IC2-REG)") (class "Default")
      (node (ref "C32") (pin "2") (pinfunction "2_2") (pintype "passive"))
      (node (ref "IC2") (pin "A2") (pinfunction "REG_A2") (pintype "bidirectional"))
    )
    (net (code "34") (name "Net-(IC3-SDO)") (class "Default")
      (node (ref "IC3") (pin "1") (pinfunction "SDO_1") (pintype "bidirectional"))
      (node (ref "R3") (pin "2") (pinfunction "2_2") (pintype "bidirectional"))
    )
    (net (code "35") (name "Net-(IC9-SCL)") (class "Default")
      (node (ref "IC9") (pin "D1") (pinfunction "SCL_D1") (pintype "bidirectional"))
      (node (ref "R4") (pin "2") (pinfunction "2_2") (pintype "bidirectional"))
    )
    (net (code "36") (name "Net-(IC9-SDA)") (class "Default")
      (node (ref "IC9") (pin "E1") (pinfunction "SDA_E1") (pintype "bidirectional"))
      (node (ref "R2") (pin "2") (pinfunction "2_2") (pintype "bidirectional"))
    )
    (net (code "37") (name "Net-(J4-CC1)") (class "Default")
      (node (ref "J4") (pin "A5") (pinfunction "CC1_A5") (pintype "bidirectional"))
      (node (ref "R1_USB") (pin "2") (pinfunction "2_2") (pintype "bidirectional"))
    )
    (net (code "38") (name "Net-(J4-CC2)") (class "Default")
      (node (ref "J4") (pin "B5") (pinfunction "CC2_B5") (pintype "bidirectional"))
      (node (ref "R2_USB") (pin "1") (pinfunction "1_1") (pintype "bidirectional"))
    )
    (net (code "39") (name "Net-(L2-Pad2)") (class "Default")
      (node (ref "L2") (pin "2") (pinfunction "2_2") (pintype "passive"))
      (node (ref "L3") (pin "1") (pinfunction "1_1") (pintype "passive"))
    )
    (net (code "40") (name "Net-(R1_EP_DR-Pad1)") (class "Default")
      (node (ref "R1_EP_DR") (pin "1") (pinfunction "1_1") (pintype "bidirectional"))
      (node (ref "R_TYPE_SEL") (pin "2") (pinfunction "2_2") (pintype "bidirectional"))
      (node (ref "SJ1") (pin "2") (pinfunction "2_2") (pintype "passive"))
    )
    (net (code "41") (name "Net-(U1-ANT)") (class "Default")
      (node (ref "C3") (pin "1") (pinfunction "1_1") (pintype "passive"))
      (node (ref "L1") (pin "1") (pinfunction "1_1") (pintype "passive"))
      (node (ref "U1") (pin "P$H23") (pinfunction "ANT_P$H23") (pintype "bidirectional"))
    )
    (net (code "42") (name "Net-(U1-DCC)") (class "Default")
      (node (ref "L2") (pin "1") (pinfunction "1_1") (pintype "passive"))
      (node (ref "U1") (pin "P$B3") (pinfunction "DCC_P$B3") (pintype "output"))
    )
    (net (code "43") (name "Net-(U1-DEC2)") (class "Default")
      (node (ref "C13") (pin "1") (pinfunction "1_1") (pintype "passive"))
      (node (ref "U1") (pin "P$A18") (pinfunction "DEC2_P$A18") (pintype "bidirectional"))
    )
    (net (code "44") (name "Net-(U1-DEC3V3)") (class "Default")
      (node (ref "C20") (pin "1") (pinfunction "1_1") (pintype "passive"))
      (node (ref "U1") (pin "P$AC5") (pinfunction "DEC3V3_P$AC5") (pintype "bidirectional"))
    )
    (net (code "45") (name "Net-(U1-DEC5)") (class "Default")
      (node (ref "C9") (pin "1") (pinfunction "1_1") (pintype "passive"))
      (node (ref "U1") (pin "P$N24") (pinfunction "DEC5_P$N24") (pintype "bidirectional"))
    )
    (net (code "46") (name "Net-(U1-XC1)") (class "Default")
      (node (ref "C1") (pin "1") (pinfunction "1_1") (pintype "passive"))
      (node (ref "U1") (pin "P$B24") (pinfunction "XC1_P$B24") (pintype "input"))
      (node (ref "X1") (pin "1") (pinfunction "1_1") (pintype "passive"))
    )
    (net (code "47") (name "Net-(U1-XC2)") (class "Default")
      (node (ref "C2") (pin "1") (pinfunction "1_1") (pintype "passive"))
      (node (ref "U1") (pin "P$A23") (pinfunction "XC2_P$A23") (pintype "output"))
      (node (ref "X1") (pin "3") (pinfunction "3_3") (pintype "passive"))
    )
    (net (code "48") (name "OUT+") (class "Default")
      (node (ref "IC2") (pin "A3") (pinfunction "OUT+_A3") (pintype "bidirectional"))
      (node (ref "TP_OP") (pin "TP") (pinfunction "TP_TP") (pintype "input"))
    )
    (net (code "49") (name "OUT-") (class "Default")
      (node (ref "IC2") (pin "C3") (pinfunction "OUT-_C3") (pintype "bidirectional"))
      (node (ref "TP_ON") (pin "TP") (pinfunction "TP_TP") (pintype "input"))
    )
    (net (code "50") (name "P0.00{slash}XL1") (class "Default")
      (node (ref "C17") (pin "2") (pinfunction "2_2") (pintype "passive"))
      (node (ref "U1") (pin "P$D2") (pinfunction "P0.00/XL1_P$D2") (pintype "bidirectional"))
      (node (ref "X2") (pin "1") (pinfunction "1_1") (pintype "passive"))
    )
    (net (code "51") (name "P0.01{slash}XL2") (class "Default")
      (node (ref "C18") (pin "2") (pinfunction "2_2") (pintype "passive"))
      (node (ref "U1") (pin "P$F2") (pinfunction "P0.01/XL2_P$F2") (pintype "bidirectional"))
      (node (ref "X2") (pin "2") (pinfunction "2_2") (pintype "passive"))
    )
    (net (code "52") (name "P0.04") (class "Default")
      (node (ref "U1") (pin "P$J1") (pinfunction "P0.04/AIN2_P$J1") (pintype "bidirectional"))
    )
    (net (code "53") (name "P0.09") (class "Default")
      (node (ref "U1") (pin "P$L24") (pinfunction "P0.09/NFC1_P$L24") (pintype "bidirectional"))
    )
    (net (code "54") (name "P0.13") (class "Default")
      (node (ref "C30") (pin "2") (pinfunction "2_2") (pintype "passive"))
      (node (ref "R5") (pin "1") (pinfunction "1_1") (pintype "bidirectional"))
      (node (ref "SW_UP") (pin "2") (pinfunction "2_2") (pintype "passive"))
      (node (ref "U1") (pin "P$AD8") (pinfunction "P0.13_P$AD8") (pintype "bidirectional"))
    )
    (net (code "55") (name "P0.14") (class "Default")
      (node (ref "C31") (pin "2") (pinfunction "2_2") (pintype "passive"))
      (node (ref "R8") (pin "1") (pinfunction "1_1") (pintype "bidirectional"))
      (node (ref "SW_ENT") (pin "2") (pinfunction "2_2") (pintype "passive"))
      (node (ref "U1") (pin "P$AC9") (pinfunction "P0.14_P$AC9") (pintype "bidirectional"))
    )
    (net (code "56") (name "P0.19") (class "Default")
      (node (ref "U1") (pin "P$AC15") (pinfunction "P0.19_P$AC15") (pintype "bidirectional"))
    )
    (net (code "57") (name "P0.20") (class "Default")
      (node (ref "U1") (pin "P$AD16") (pinfunction "P0.20_P$AD16") (pintype "bidirectional"))
    )
    (net (code "58") (name "P0.21") (class "Default")
      (node (ref "U1") (pin "P$AC17") (pinfunction "P0.21_P$AC17") (pintype "bidirectional"))
    )
    (net (code "59") (name "P0.22") (class "Default")
      (node (ref "U1") (pin "P$AD18") (pinfunction "P0.22_P$AD18") (pintype "bidirectional"))
    )
    (net (code "60") (name "P0.23") (class "Default")
      (node (ref "U1") (pin "P$AC19") (pinfunction "P0.23_P$AC19") (pintype "bidirectional"))
    )
    (net (code "61") (name "P0.24") (class "Default")
      (node (ref "U1") (pin "P$AD20") (pinfunction "P0.24_P$AD20") (pintype "bidirectional"))
    )
    (net (code "62") (name "P0.25") (class "Default")
      (node (ref "U1") (pin "P$AC21") (pinfunction "P0.25_P$AC21") (pintype "bidirectional"))
    )
    (net (code "63") (name "P0.26") (class "Default")
      (node (ref "U1") (pin "P$G1") (pinfunction "P0.26_P$G1") (pintype "bidirectional"))
    )
    (net (code "64") (name "P0.27") (class "Default")
      (node (ref "U1") (pin "P$H2") (pinfunction "P0.27_P$H2") (pintype "bidirectional"))
    )
    (net (code "65") (name "P0.28") (class "Default")
      (node (ref "U1") (pin "P$B11") (pinfunction "P0.28/AIN4_P$B11") (pintype "bidirectional"))
    )
    (net (code "66") (name "P0.29") (class "Default")
      (node (ref "U1") (pin "P$A10") (pinfunction "P0.29/AIN5_P$A10") (pintype "bidirectional"))
    )
    (net (code "67") (name "P0.30") (class "Default")
      (node (ref "U1") (pin "P$B9") (pinfunction "P0.30/AIN6_P$B9") (pintype "bidirectional"))
    )
    (net (code "68") (name "P0.31") (class "Default")
      (node (ref "U1") (pin "P$A8") (pinfunction "P0.31/AIN7_P$A8") (pintype "bidirectional"))
    )
    (net (code "69") (name "P1.01") (class "Default")
      (node (ref "Q1") (pin "1") (pinfunction "G_1") (pintype "bidirectional"))
      (node (ref "R_PWR_EPD") (pin "1") (pinfunction "1_1") (pintype "bidirectional"))
      (node (ref "U1") (pin "P$Y23") (pinfunction "P1.01_P$Y23") (pintype "bidirectional"))
    )
    (net (code "70") (name "P1.02") (class "Default")
      (node (ref "C29") (pin "2") (pinfunction "2_2") (pintype "passive"))
      (node (ref "R7") (pin "1") (pinfunction "1_1") (pintype "bidirectional"))
      (node (ref "SW_DN") (pin "2") (pinfunction "2_2") (pintype "passive"))
      (node (ref "U1") (pin "P$W24") (pinfunction "P1.02_P$W24") (pintype "bidirectional"))
    )
    (net (code "71") (name "P1.03") (class "Default")
      (node (ref "U1") (pin "P$V23") (pinfunction "P1.03_P$V23") (pintype "bidirectional"))
    )
    (net (code "72") (name "P1.04") (class "Default")
      (node (ref "U1") (pin "P$U24") (pinfunction "P1.04_P$U24") (pintype "bidirectional"))
    )
    (net (code "73") (name "P1.05") (class "Default")
      (node (ref "U1") (pin "P$T23") (pinfunction "P1.05_P$T23") (pintype "bidirectional"))
    )
    (net (code "74") (name "P1.06") (class "Default")
      (node (ref "U1") (pin "P$R24") (pinfunction "P1.06_P$R24") (pintype "bidirectional"))
    )
    (net (code "75") (name "P1.07") (class "Default")
      (node (ref "U1") (pin "P$P23") (pinfunction "P1.07_P$P23") (pintype "bidirectional"))
    )
    (net (code "76") (name "P1.09") (class "Default")
      (node (ref "U1") (pin "P$R1") (pinfunction "P1.09_P$R1") (pintype "bidirectional"))
    )
    (net (code "77") (name "P1.10") (class "Default")
      (node (ref "U1") (pin "P$A20") (pinfunction "P1.10_P$A20") (pintype "bidirectional"))
    )
    (net (code "78") (name "P1.11") (class "Default")
      (node (ref "U1") (pin "P$B19") (pinfunction "P1.11_P$B19") (pintype "bidirectional"))
    )
    (net (code "79") (name "P1.12") (class "Default")
      (node (ref "U1") (pin "P$B17") (pinfunction "P1.12_P$B17") (pintype "bidirectional"))
    )
    (net (code "80") (name "P1.13") (class "Default")
      (node (ref "U1") (pin "P$A16") (pinfunction "P1.13_P$A16") (pintype "bidirectional"))
    )
    (net (code "81") (name "P1.14") (class "Default")
      (node (ref "U1") (pin "P$B15") (pinfunction "P1.14_P$B15") (pintype "bidirectional"))
    )
    (net (code "82") (name "P1.15") (class "Default")
      (node (ref "U1") (pin "P$A14") (pinfunction "P1.15_P$A14") (pintype "bidirectional"))
    )
    (net (code "83") (name "PMIC_INT") (class "Default")
      (node (ref "IC1") (pin "A1") (pinfunction "~{INT}_A1") (pintype "bidirectional"))
      (node (ref "U1") (pin "P$T2") (pinfunction "P0.11_P$T2") (pintype "bidirectional"))
    )
    (net (code "84") (name "PREVGH") (class "Default")
      (node (ref "D5") (pin "1") (pinfunction "K_1") (pintype "bidirectional"))
      (node (ref "EPD_C9") (pin "2") (pinfunction "2_2") (pintype "passive"))
      (node (ref "J1") (pin "21") (pinfunction "21_21") (pintype "bidirectional"))
    )
    (net (code "85") (name "PREVGL") (class "Default")
      (node (ref "D2") (pin "2") (pinfunction "A_2") (pintype "bidirectional"))
      (node (ref "EPD_C11") (pin "2") (pinfunction "2_2") (pintype "passive"))
      (node (ref "J1") (pin "23") (pinfunction "23_23") (pintype "bidirectional"))
    )
    (net (code "86") (name "RESE") (class "Default")
      (node (ref "J1") (pin "3") (pinfunction "3_3") (pintype "bidirectional"))
      (node (ref "Q3") (pin "2") (pinfunction "S_2") (pintype "bidirectional"))
      (node (ref "R1_EP_DR") (pin "2") (pinfunction "2_2") (pintype "bidirectional"))
    )
    (net (code "87") (name "RESET") (class "Default")
      (node (ref "J2") (pin "6") (pinfunction "6_6") (pintype "bidirectional"))
      (node (ref "TP_RESET") (pin "TP") (pinfunction "TP_TP") (pintype "input"))
      (node (ref "U1") (pin "P$AC13") (pinfunction "P0.18/RESET_P$AC13") (pintype "bidirectional"))
    )
    (net (code "88") (name "RF") (class "Default")
      (node (ref "ANT1") (pin "1") (pinfunction "FEED_1") (pintype "input"))
      (node (ref "C22") (pin "1") (pinfunction "1_1") (pintype "passive"))
      (node (ref "C4") (pin "1") (pinfunction "1_1") (pintype "passive"))
      (node (ref "L1") (pin "2") (pinfunction "2_2") (pintype "passive"))
    )
    (net (code "89") (name "SCK") (class "Default")
      (node (ref "J1") (pin "13") (pinfunction "13_13") (pintype "bidirectional"))
      (node (ref "U1") (pin "P$A12") (pinfunction "P0.02/AIN0_P$A12") (pintype "bidirectional"))
    )
    (net (code "90") (name "SCL") (class "Default")
      (node (ref "IC1") (pin "B1") (pinfunction "SCL_B1") (pintype "bidirectional"))
      (node (ref "IC2") (pin "C1") (pinfunction "SCL_C1") (pintype "bidirectional"))
      (node (ref "IC3") (pin "12") (pinfunction "SCX_12") (pintype "bidirectional"))
      (node (ref "R17") (pin "2") (pinfunction "2_2") (pintype "bidirectional"))
      (node (ref "R4") (pin "1") (pinfunction "1_1") (pintype "bidirectional"))
      (node (ref "TP_SCL") (pin "TP") (pinfunction "TP_TP") (pintype "input"))
      (node (ref "U1") (pin "P$M2") (pinfunction "P0.07_P$M2") (pintype "bidirectional"))
      (node (ref "U3") (pin "7") (pinfunction "SCL_7") (pintype "input"))
    )
    (net (code "91") (name "SDA") (class "Default")
      (node (ref "IC1") (pin "C1") (pinfunction "SDA_C1") (pintype "bidirectional"))
      (node (ref "IC2") (pin "B2") (pinfunction "SDA_B2") (pintype "bidirectional"))
      (node (ref "IC3") (pin "2") (pinfunction "SDX_2") (pintype "bidirectional"))
      (node (ref "R18") (pin "2") (pinfunction "2_2") (pintype "bidirectional"))
      (node (ref "R2") (pin "1") (pinfunction "1_1") (pintype "bidirectional"))
      (node (ref "TP_SDA") (pin "TP") (pinfunction "TP_TP") (pintype "input"))
      (node (ref "U1") (pin "P$L1") (pinfunction "P0.06_P$L1") (pintype "bidirectional"))
      (node (ref "U3") (pin "8") (pinfunction "SDA_8") (pintype "bidirectional"))
    )
    (net (code "92") (name "SWDCLK") (class "Default")
      (node (ref "J2") (pin "4") (pinfunction "4_4") (pintype "bidirectional"))
      (node (ref "TP_SWDCLK") (pin "TP") (pinfunction "TP_TP") (pintype "input"))
      (node (ref "U1") (pin "P$AC24") (pinfunction "SWDIO_P$AC24") (pintype "bidirectional"))
    )
    (net (code "93") (name "SWDIO") (class "Default")
      (node (ref "J2") (pin "2") (pinfunction "2_2") (pintype "bidirectional"))
      (node (ref "TP_SWDIO") (pin "TP") (pinfunction "TP_TP") (pintype "input"))
      (node (ref "U1") (pin "P$AA24") (pinfunction "SWDCLK_P$AA24") (pintype "input"))
    )
    (net (code "94") (name "SWO") (class "Default")
      (node (ref "TP_SWO") (pin "TP") (pinfunction "TP_TP") (pintype "input"))
      (node (ref "U1") (pin "P$AD22") (pinfunction "P1.00_P$AD22") (pintype "bidirectional"))
    )
    (net (code "95") (name "VBAT") (class "Default")
      (node (ref "C27") (pin "2") (pinfunction "2_2") (pintype "passive"))
      (node (ref "C37") (pin "2") (pinfunction "2_2") (pintype "passive"))
      (node (ref "IC1") (pin "C2") (pinfunction "BAT_C2") (pintype "bidirectional"))
      (node (ref "TP_VBAT") (pin "TP") (pinfunction "TP_TP") (pintype "input"))
      (node (ref "U3") (pin "2") (pinfunction "CELL_2") (pintype "power_in"))
      (node (ref "U3") (pin "3") (pinfunction "VDD_3") (pintype "power_in"))
    )
    (net (code "96") (name "VBUS") (class "Default")
      (node (ref "C21") (pin "1") (pinfunction "1_1") (pintype "passive"))
      (node (ref "C38") (pin "2") (pinfunction "2_2") (pintype "passive"))
      (node (ref "C42") (pin "1") (pinfunction "1_1") (pintype "passive"))
      (node (ref "C43") (pin "1") (pinfunction "1_1") (pintype "passive"))
      (node (ref "D3") (pin "5") (pinfunction "VBUS_5") (pintype "bidirectional"))
      (node (ref "IC1") (pin "A2") (pinfunction "IN_A2") (pintype "bidirectional"))
      (node (ref "J4") (pin "A4_B9") (pinfunction "VBUS_A4_B9") (pintype "power_in"))
      (node (ref "J4") (pin "A9_B4") (pinfunction "VBUS_A9_B4") (pintype "power_in"))
      (node (ref "U1") (pin "P$AD2") (pinfunction "VBUS_P$AD2") (pintype "power_in"))
    )
    (net (code "97") (name "VREG") (class "Default")
      (node (ref "C23") (pin "2") (pinfunction "2_2") (pintype "passive"))
      (node (ref "C24") (pin "2") (pinfunction "2_2") (pintype "passive"))
      (node (ref "C39") (pin "1") (pinfunction "1_1") (pintype "passive"))
      (node (ref "IC1") (pin "B2") (pinfunction "SYS_B2") (pintype "bidirectional"))
      (node (ref "IC9") (pin "A1") (pinfunction "EN_A1") (pintype "bidirectional"))
      (node (ref "IC9") (pin "A2") (pinfunction "VIN_1_A2") (pintype "bidirectional"))
      (node (ref "IC9") (pin "A3") (pinfunction "VIN_2_A3") (pintype "bidirectional"))
      (node (ref "TP_VREG") (pin "TP") (pinfunction "TP_TP") (pintype "input"))
    )
    (net (code "98") (name "unconnected-(ANT1-NC-Pad2)") (class "Default")
      (node (ref "ANT1") (pin "2") (pinfunction "NC_2") (pintype "no_connect"))
    )
    (net (code "99") (name "unconnected-(IC3-ASCL-Pad11)") (class "Default")
      (node (ref "IC3") (pin "11") (pinfunction "ASCL_11") (pintype "bidirectional"))
    )
    (net (code "100") (name "unconnected-(IC3-ASDA-Pad4)") (class "Default")
      (node (ref "IC3") (pin "4") (pinfunction "ASDA_4") (pintype "bidirectional"))
    )
    (net (code "101") (name "unconnected-(J1-Pad1)") (class "Default")
      (node (ref "J1") (pin "1") (pinfunction "1_1") (pintype "bidirectional"))
    )
    (net (code "102") (name "unconnected-(J1-Pad6)") (class "Default")
      (node (ref "J1") (pin "6") (pinfunction "6_6") (pintype "bidirectional"))
    )
    (net (code "103") (name "unconnected-(J1-Pad7)") (class "Default")
      (node (ref "J1") (pin "7") (pinfunction "7_7") (pintype "bidirectional"))
    )
    (net (code "104") (name "unconnected-(J4-SBU1-PadA8)") (class "Default")
      (node (ref "J4") (pin "A8") (pinfunction "SBU1_A8") (pintype "bidirectional"))
    )
    (net (code "105") (name "unconnected-(J4-SBU2-PadB8)") (class "Default")
      (node (ref "J4") (pin "B8") (pinfunction "SBU2_B8") (pintype "bidirectional"))
    )
    (net (code "106") (name "unconnected-(U1-DCCH-PadP$AB2)") (class "Default")
      (node (ref "U1") (pin "P$AB2") (pinfunction "DCCH_P$AB2") (pintype "bidirectional"))
    )
  )
)
